# KSZ_Switch_Control.net
KiCad netlist of a schematic drawn in Altium Designer
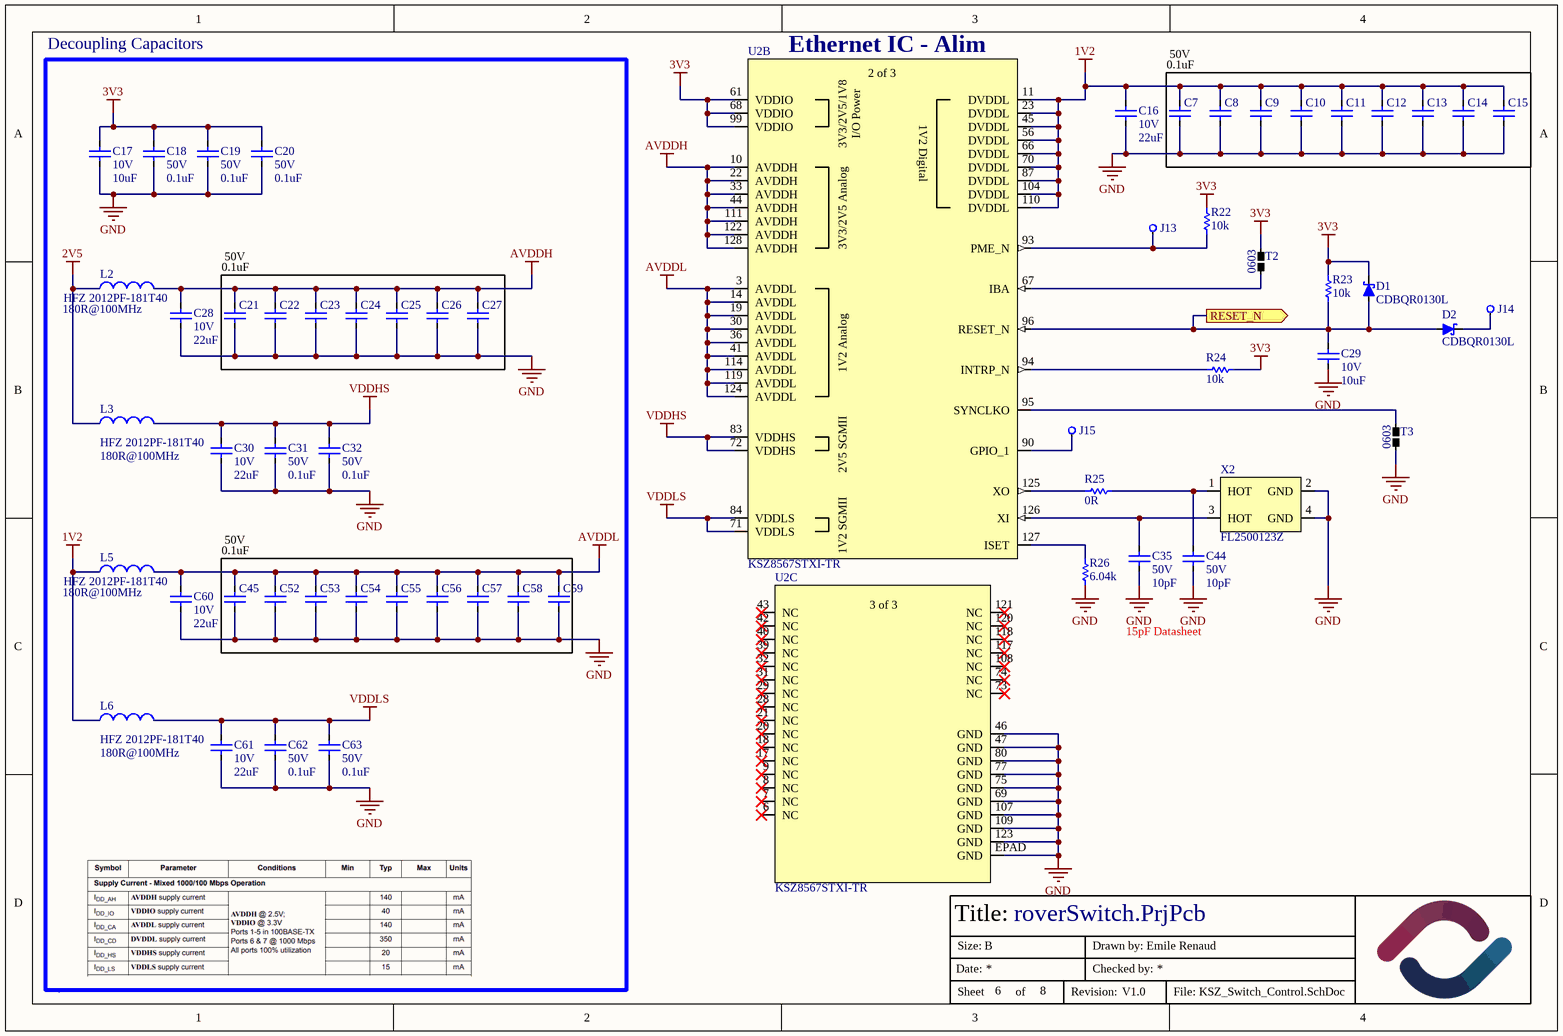
[diagram p0: KSZ_Switch_Control.SchDoc]

(export (version "E")
  (design (tool "Eeschema 10.0.6"))
  (components
    (comp (ref "C7")
      (value "Capacitor-0603-0.1uF-50V-X7R")
      (footprint "CAPACITOR-0603")
      (libsource (lib "Capacitors") (part "Capacitor-0603-0.1uF-50V-X7R"))
    )
    (comp (ref "C8")
      (value "Capacitor-0603-0.1uF-50V-X7R")
      (footprint "CAPACITOR-0603")
      (libsource (lib "Capacitors") (part "Capacitor-0603-0.1uF-50V-X7R"))
    )
    (comp (ref "C9")
      (value "Capacitor-0603-0.1uF-50V-X7R")
      (footprint "CAPACITOR-0603")
      (libsource (lib "Capacitors") (part "Capacitor-0603-0.1uF-50V-X7R"))
    )
    (comp (ref "C10")
      (value "Capacitor-0603-0.1uF-50V-X7R")
      (footprint "CAPACITOR-0603")
      (libsource (lib "Capacitors") (part "Capacitor-0603-0.1uF-50V-X7R"))
    )
    (comp (ref "C11")
      (value "Capacitor-0603-0.1uF-50V-X7R")
      (footprint "CAPACITOR-0603")
      (libsource (lib "Capacitors") (part "Capacitor-0603-0.1uF-50V-X7R"))
    )
    (comp (ref "C12")
      (value "Capacitor-0603-0.1uF-50V-X7R")
      (footprint "CAPACITOR-0603")
      (libsource (lib "Capacitors") (part "Capacitor-0603-0.1uF-50V-X7R"))
    )
    (comp (ref "C13")
      (value "Capacitor-0603-0.1uF-50V-X7R")
      (footprint "CAPACITOR-0603")
      (libsource (lib "Capacitors") (part "Capacitor-0603-0.1uF-50V-X7R"))
    )
    (comp (ref "C14")
      (value "Capacitor-0603-0.1uF-50V-X7R")
      (footprint "CAPACITOR-0603")
      (libsource (lib "Capacitors") (part "Capacitor-0603-0.1uF-50V-X7R"))
    )
    (comp (ref "C15")
      (value "Capacitor-0603-0.1uF-50V-X7R")
      (footprint "CAPACITOR-0603")
      (libsource (lib "Capacitors") (part "Capacitor-0603-0.1uF-50V-X7R"))
    )
    (comp (ref "C16")
      (value "22uF")
      (footprint "CAPACITOR-0603")
      (description "Capacitor-0603-22uF-10V-X5R")
      (fields (field (name "VOLT") "10V"))
      (libsource (lib "Capacitors") (part "Capacitor-0603-22uF-10V-X5R"))
    )
    (comp (ref "C17")
      (value "10uF")
      (footprint "CAPACITOR-0603")
      (description "10 µF ±20% 10V Ceramic Capacitor X5R 0603 (1608 Metric)")
      (fields (field (name "VOLT") "10V") (field (name "Comment") "Capacitor-0603-10uF-10V-X5R"))
      (libsource (lib "Capacitors") (part "Capacitor-0603-10uF-10V-X5R"))
    )
    (comp (ref "C18")
      (value "0.1uF")
      (footprint "CAPACITOR-0603")
      (description "Capacitor-0603-0.1uF-50V-X7R")
      (fields (field (name "VOLT") "50V"))
      (libsource (lib "Capacitors") (part "Capacitor-0603-0.1uF-50V-X7R"))
    )
    (comp (ref "C19")
      (value "0.1uF")
      (footprint "CAPACITOR-0603")
      (description "Capacitor-0603-0.1uF-50V-X7R")
      (fields (field (name "VOLT") "50V"))
      (libsource (lib "Capacitors") (part "Capacitor-0603-0.1uF-50V-X7R"))
    )
    (comp (ref "C20")
      (value "0.1uF")
      (footprint "CAPACITOR-0603")
      (description "Capacitor-0603-0.1uF-50V-X7R")
      (fields (field (name "VOLT") "50V"))
      (libsource (lib "Capacitors") (part "Capacitor-0603-0.1uF-50V-X7R"))
    )
    (comp (ref "C21")
      (value "Capacitor-0603-0.1uF-50V-X7R")
      (footprint "CAPACITOR-0603")
      (libsource (lib "Capacitors") (part "Capacitor-0603-0.1uF-50V-X7R"))
    )
    (comp (ref "C22")
      (value "Capacitor-0603-0.1uF-50V-X7R")
      (footprint "CAPACITOR-0603")
      (libsource (lib "Capacitors") (part "Capacitor-0603-0.1uF-50V-X7R"))
    )
    (comp (ref "C23")
      (value "Capacitor-0603-0.1uF-50V-X7R")
      (footprint "CAPACITOR-0603")
      (libsource (lib "Capacitors") (part "Capacitor-0603-0.1uF-50V-X7R"))
    )
    (comp (ref "C24")
      (value "Capacitor-0603-0.1uF-50V-X7R")
      (footprint "CAPACITOR-0603")
      (libsource (lib "Capacitors") (part "Capacitor-0603-0.1uF-50V-X7R"))
    )
    (comp (ref "C25")
      (value "Capacitor-0603-0.1uF-50V-X7R")
      (footprint "CAPACITOR-0603")
      (libsource (lib "Capacitors") (part "Capacitor-0603-0.1uF-50V-X7R"))
    )
    (comp (ref "C26")
      (value "Capacitor-0603-0.1uF-50V-X7R")
      (footprint "CAPACITOR-0603")
      (libsource (lib "Capacitors") (part "Capacitor-0603-0.1uF-50V-X7R"))
    )
    (comp (ref "C27")
      (value "Capacitor-0603-0.1uF-50V-X7R")
      (footprint "CAPACITOR-0603")
      (libsource (lib "Capacitors") (part "Capacitor-0603-0.1uF-50V-X7R"))
    )
    (comp (ref "C28")
      (value "22uF")
      (footprint "CAPACITOR-0603")
      (description "Capacitor-0603-22uF-10V-X5R")
      (fields (field (name "VOLT") "10V"))
      (libsource (lib "Capacitors") (part "Capacitor-0603-22uF-10V-X5R"))
    )
    (comp (ref "C29")
      (value "10uF")
      (footprint "CAPACITOR-0603")
      (description "10 µF ±20% 10V Ceramic Capacitor X5R 0603 (1608 Metric)")
      (fields (field (name "VOLT") "10V") (field (name "Comment") "Capacitor-0603-10uF-10V-X5R"))
      (libsource (lib "Capacitors") (part "Capacitor-0603-10uF-10V-X5R"))
    )
    (comp (ref "C30")
      (value "22uF")
      (footprint "CAPACITOR-0603")
      (description "Capacitor-0603-22uF-10V-X5R")
      (fields (field (name "VOLT") "10V"))
      (libsource (lib "Capacitors") (part "Capacitor-0603-22uF-10V-X5R"))
    )
    (comp (ref "C31")
      (value "0.1uF")
      (footprint "CAPACITOR-0603")
      (description "Capacitor-0603-0.1uF-50V-X7R")
      (fields (field (name "VOLT") "50V"))
      (libsource (lib "Capacitors") (part "Capacitor-0603-0.1uF-50V-X7R"))
    )
    (comp (ref "C32")
      (value "0.1uF")
      (footprint "CAPACITOR-0603")
      (description "Capacitor-0603-0.1uF-50V-X7R")
      (fields (field (name "VOLT") "50V"))
      (libsource (lib "Capacitors") (part "Capacitor-0603-0.1uF-50V-X7R"))
    )
    (comp (ref "C35")
      (value "10pF")
      (footprint "CAPACITOR-0402")
      (description "Capacitor-0402-10pF-50V-C0G")
      (fields (field (name "VOLT") "50V"))
      (libsource (lib "Capacitors") (part "Capacitor-0402-10pF-50V-C0G"))
    )
    (comp (ref "C44")
      (value "10pF")
      (footprint "CAPACITOR-0402")
      (description "Capacitor-0402-10pF-50V-C0G")
      (fields (field (name "VOLT") "50V"))
      (libsource (lib "Capacitors") (part "Capacitor-0402-10pF-50V-C0G"))
    )
    (comp (ref "C45")
      (value "Capacitor-0603-0.1uF-50V-X7R")
      (footprint "CAPACITOR-0603")
      (libsource (lib "Capacitors") (part "Capacitor-0603-0.1uF-50V-X7R"))
    )
    (comp (ref "C52")
      (value "Capacitor-0603-0.1uF-50V-X7R")
      (footprint "CAPACITOR-0603")
      (libsource (lib "Capacitors") (part "Capacitor-0603-0.1uF-50V-X7R"))
    )
    (comp (ref "C53")
      (value "Capacitor-0603-0.1uF-50V-X7R")
      (footprint "CAPACITOR-0603")
      (libsource (lib "Capacitors") (part "Capacitor-0603-0.1uF-50V-X7R"))
    )
    (comp (ref "C54")
      (value "Capacitor-0603-0.1uF-50V-X7R")
      (footprint "CAPACITOR-0603")
      (libsource (lib "Capacitors") (part "Capacitor-0603-0.1uF-50V-X7R"))
    )
    (comp (ref "C55")
      (value "Capacitor-0603-0.1uF-50V-X7R")
      (footprint "CAPACITOR-0603")
      (libsource (lib "Capacitors") (part "Capacitor-0603-0.1uF-50V-X7R"))
    )
    (comp (ref "C56")
      (value "Capacitor-0603-0.1uF-50V-X7R")
      (footprint "CAPACITOR-0603")
      (libsource (lib "Capacitors") (part "Capacitor-0603-0.1uF-50V-X7R"))
    )
    (comp (ref "C57")
      (value "Capacitor-0603-0.1uF-50V-X7R")
      (footprint "CAPACITOR-0603")
      (libsource (lib "Capacitors") (part "Capacitor-0603-0.1uF-50V-X7R"))
    )
    (comp (ref "C58")
      (value "Capacitor-0603-0.1uF-50V-X7R")
      (footprint "CAPACITOR-0603")
      (libsource (lib "Capacitors") (part "Capacitor-0603-0.1uF-50V-X7R"))
    )
    (comp (ref "C59")
      (value "Capacitor-0603-0.1uF-50V-X7R")
      (footprint "CAPACITOR-0603")
      (libsource (lib "Capacitors") (part "Capacitor-0603-0.1uF-50V-X7R"))
    )
    (comp (ref "C60")
      (value "22uF")
      (footprint "CAPACITOR-0603")
      (description "Capacitor-0603-22uF-10V-X5R")
      (fields (field (name "VOLT") "10V"))
      (libsource (lib "Capacitors") (part "Capacitor-0603-22uF-10V-X5R"))
    )
    (comp (ref "C61")
      (value "22uF")
      (footprint "CAPACITOR-0603")
      (description "Capacitor-0603-22uF-10V-X5R")
      (fields (field (name "VOLT") "10V"))
      (libsource (lib "Capacitors") (part "Capacitor-0603-22uF-10V-X5R"))
    )
    (comp (ref "C62")
      (value "0.1uF")
      (footprint "CAPACITOR-0603")
      (description "Capacitor-0603-0.1uF-50V-X7R")
      (fields (field (name "VOLT") "50V"))
      (libsource (lib "Capacitors") (part "Capacitor-0603-0.1uF-50V-X7R"))
    )
    (comp (ref "C63")
      (value "0.1uF")
      (footprint "CAPACITOR-0603")
      (description "Capacitor-0603-0.1uF-50V-X7R")
      (fields (field (name "VOLT") "50V"))
      (libsource (lib "Capacitors") (part "Capacitor-0603-0.1uF-50V-X7R"))
    )
    (comp (ref "D1")
      (value "CDBQR0130L")
      (footprint "Diode-0402")
      (description "Diode SCHOTTKY  30 V 100mA Surface Mount 0402/SOD-923F")
      (libsource (lib "diodes") (part "CDBQR0130L"))
    )
    (comp (ref "D2")
      (value "CDBQR0130L")
      (footprint "Diode-0402")
      (description "Diode SCHOTTKY  30 V 100mA Surface Mount 0402/SOD-923F")
      (libsource (lib "diodes") (part "CDBQR0130L"))
    )
    (comp (ref "J13")
      (value "hole")
      (footprint "PCB_Footprints:PAD-0.53MM")
      (description "PAD for 28 AWG Solid Wire")
      (libsource (lib "JumpersAndHoles") (part "PAD 0.53mm AWG28-Solid"))
    )
    (comp (ref "J14")
      (value "hole")
      (footprint "PCB_Footprints:PAD-0.53MM")
      (description "PAD for 28 AWG Solid Wire")
      (libsource (lib "JumpersAndHoles") (part "PAD 0.53mm AWG28-Solid"))
    )
    (comp (ref "J15")
      (value "hole")
      (footprint "PCB_Footprints:PAD-0.53MM")
      (description "PAD for 28 AWG Solid Wire")
      (libsource (lib "JumpersAndHoles") (part "PAD 0.53mm AWG28-Solid"))
    )
    (comp (ref "L2")
      (value "HFZ 2012PF-181T40")
      (footprint "CAPACITOR-0805")
      (description "180 Ohms @ 100 MHz 1 Power Line Ferrite Bead 0805 (2012 Metric) 4A 20mOhm")
      (fields (field (name "ALTIUM_VALUE") "180R@100MHz"))
      (libsource (lib "Inductors") (part "HFZ 2012PF-181T40"))
    )
    (comp (ref "L3")
      (value "HFZ 2012PF-181T40")
      (footprint "CAPACITOR-0805")
      (description "180 Ohms @ 100 MHz 1 Power Line Ferrite Bead 0805 (2012 Metric) 4A 20mOhm")
      (fields (field (name "ALTIUM_VALUE") "180R@100MHz"))
      (libsource (lib "Inductors") (part "HFZ 2012PF-181T40"))
    )
    (comp (ref "L5")
      (value "HFZ 2012PF-181T40")
      (footprint "CAPACITOR-0805")
      (description "180 Ohms @ 100 MHz 1 Power Line Ferrite Bead 0805 (2012 Metric) 4A 20mOhm")
      (fields (field (name "ALTIUM_VALUE") "180R@100MHz"))
      (libsource (lib "Inductors") (part "HFZ 2012PF-181T40"))
    )
    (comp (ref "L6")
      (value "HFZ 2012PF-181T40")
      (footprint "CAPACITOR-0805")
      (description "180 Ohms @ 100 MHz 1 Power Line Ferrite Bead 0805 (2012 Metric) 4A 20mOhm")
      (fields (field (name "ALTIUM_VALUE") "180R@100MHz"))
      (libsource (lib "Inductors") (part "HFZ 2012PF-181T40"))
    )
    (comp (ref "R22")
      (value "10k")
      (footprint "Resistor-0603")
      (description "Resistor0603-10k")
      (fields (field (name "Comment") "SMT resistor"))
      (libsource (lib "Resistors") (part "Resistor-0603-10k"))
    )
    (comp (ref "R23")
      (value "10k")
      (footprint "Resistor-0603")
      (description "Resistor0603-10k")
      (fields (field (name "Comment") "SMT resistor"))
      (libsource (lib "Resistors") (part "Resistor-0603-10k"))
    )
    (comp (ref "R24")
      (value "10k")
      (footprint "Resistor-0603")
      (description "Resistor0603-10k")
      (fields (field (name "Comment") "SMT resistor"))
      (libsource (lib "Resistors") (part "Resistor-0603-10k"))
    )
    (comp (ref "R25")
      (value "0R")
      (footprint "Resistor-0402")
      (description "Resistor-0402-0R")
      (fields (field (name "Comment") "SMT resistor"))
      (libsource (lib "Resistors") (part "Resistor-0402-0R"))
    )
    (comp (ref "R26")
      (value "6.04k")
      (footprint "Resistor-0603")
      (description "Resistor-0603-6.04k")
      (fields (field (name "Comment") "SMT resistor"))
      (libsource (lib "Resistors") (part "Resistor-0603-6.04k"))
    )
    (comp (ref "T2")
      (value "NetTie_0603")
      (footprint "NetTie-0603-short")
      (libsource (lib "JumpersAndHoles") (part "NetTie_0603_Short"))
    )
    (comp (ref "T3")
      (value "NetTie_0603_Short")
      (footprint "NetTie-0603-short")
      (libsource (lib "JumpersAndHoles") (part "NetTie_0603_Short"))
    )
    (comp (ref "U2")
      (value "KSZ8567STXI-TR")
      (footprint "TQFP128_EP_6XX_MCH-M")
      (description "IC ETHERNET SWITCH 7PORT 128TQFP")
      (libsource (lib "Ethernet") (part "KSZ8567STXI-TR"))
    )
    (comp (ref "X2")
      (value "FL2500123Z")
      (footprint "4-SMD")
      (description "25 MHz ±30ppm Crystal 20pF 50 Ohms 4-SMD, No Lead")
      (libsource (lib "Crystals") (part "FL2500123Z"))
    )
  )
  (nets
    (net (code "1") (name "/RESET_N") (class "Default")
      (node (ref "C29") (pin "2") (pinfunction "2_2") (pintype "passive"))
      (node (ref "D1") (pin "1") (pinfunction "A_1") (pintype "passive"))
      (node (ref "D2") (pin "1") (pinfunction "A_1") (pintype "passive"))
      (node (ref "R23") (pin "1") (pinfunction "1_1") (pintype "passive"))
      (node (ref "U2") (pin "96") (pinfunction "RESET_N_96") (pintype "input"))
    )
    (net (code "2") (name "1V2") (class "Default")
      (node (ref "C10") (pin "2") (pinfunction "2_2") (pintype "passive"))
      (node (ref "C11") (pin "2") (pinfunction "2_2") (pintype "passive"))
      (node (ref "C12") (pin "2") (pinfunction "2_2") (pintype "passive"))
      (node (ref "C13") (pin "2") (pinfunction "2_2") (pintype "passive"))
      (node (ref "C14") (pin "2") (pinfunction "2_2") (pintype "passive"))
      (node (ref "C15") (pin "2") (pinfunction "2_2") (pintype "passive"))
      (node (ref "C16") (pin "2") (pinfunction "2_2") (pintype "passive"))
      (node (ref "C7") (pin "2") (pinfunction "2_2") (pintype "passive"))
      (node (ref "C8") (pin "2") (pinfunction "2_2") (pintype "passive"))
      (node (ref "C9") (pin "2") (pinfunction "2_2") (pintype "passive"))
      (node (ref "L5") (pin "1") (pinfunction "1_1") (pintype "passive"))
      (node (ref "L6") (pin "1") (pinfunction "1_1") (pintype "passive"))
      (node (ref "U2") (pin "104") (pinfunction "DVDDL_104") (pintype "power_in"))
      (node (ref "U2") (pin "11") (pinfunction "DVDDL_11") (pintype "power_in"))
      (node (ref "U2") (pin "110") (pinfunction "DVDDL_110") (pintype "power_in"))
      (node (ref "U2") (pin "23") (pinfunction "DVDDL_23") (pintype "power_in"))
      (node (ref "U2") (pin "45") (pinfunction "DVDDL_45") (pintype "power_in"))
      (node (ref "U2") (pin "56") (pinfunction "DVDDL_56") (pintype "power_in"))
      (node (ref "U2") (pin "66") (pinfunction "DVDDL_66") (pintype "power_in"))
      (node (ref "U2") (pin "70") (pinfunction "DVDDL_70") (pintype "power_in"))
      (node (ref "U2") (pin "87") (pinfunction "DVDDL_87") (pintype "power_in"))
    )
    (net (code "3") (name "2V5") (class "Default")
      (node (ref "L2") (pin "1") (pinfunction "1_1") (pintype "passive"))
      (node (ref "L3") (pin "1") (pinfunction "1_1") (pintype "passive"))
    )
    (net (code "4") (name "3V3") (class "Default")
      (node (ref "C17") (pin "2") (pinfunction "2_2") (pintype "passive"))
      (node (ref "C18") (pin "2") (pinfunction "2_2") (pintype "passive"))
      (node (ref "C19") (pin "2") (pinfunction "2_2") (pintype "passive"))
      (node (ref "C20") (pin "2") (pinfunction "2_2") (pintype "passive"))
      (node (ref "D1") (pin "2") (pinfunction "K_2") (pintype "passive"))
      (node (ref "R22") (pin "2") (pinfunction "2_2") (pintype "passive"))
      (node (ref "R23") (pin "2") (pinfunction "2_2") (pintype "passive"))
      (node (ref "R24") (pin "2") (pinfunction "2_2") (pintype "passive"))
      (node (ref "T2") (pin "1") (pinfunction "1_1") (pintype "passive"))
      (node (ref "U2") (pin "61") (pinfunction "VDDIO_61") (pintype "power_in"))
      (node (ref "U2") (pin "68") (pinfunction "VDDIO_68") (pintype "power_in"))
      (node (ref "U2") (pin "99") (pinfunction "VDDIO_99") (pintype "power_in"))
    )
    (net (code "5") (name "AVDDH") (class "Default")
      (node (ref "C21") (pin "2") (pinfunction "2_2") (pintype "passive"))
      (node (ref "C22") (pin "2") (pinfunction "2_2") (pintype "passive"))
      (node (ref "C23") (pin "2") (pinfunction "2_2") (pintype "passive"))
      (node (ref "C24") (pin "2") (pinfunction "2_2") (pintype "passive"))
      (node (ref "C25") (pin "2") (pinfunction "2_2") (pintype "passive"))
      (node (ref "C26") (pin "2") (pinfunction "2_2") (pintype "passive"))
      (node (ref "C27") (pin "2") (pinfunction "2_2") (pintype "passive"))
      (node (ref "C28") (pin "2") (pinfunction "2_2") (pintype "passive"))
      (node (ref "L2") (pin "2") (pinfunction "2_2") (pintype "passive"))
      (node (ref "U2") (pin "10") (pinfunction "AVDDH_10") (pintype "power_in"))
      (node (ref "U2") (pin "111") (pinfunction "AVDDH_111") (pintype "power_in"))
      (node (ref "U2") (pin "122") (pinfunction "AVDDH_122") (pintype "power_in"))
      (node (ref "U2") (pin "128") (pinfunction "AVDDH_128") (pintype "power_in"))
      (node (ref "U2") (pin "22") (pinfunction "AVDDH_22") (pintype "power_in"))
      (node (ref "U2") (pin "33") (pinfunction "AVDDH_33") (pintype "power_in"))
      (node (ref "U2") (pin "44") (pinfunction "AVDDH_44") (pintype "power_in"))
    )
    (net (code "6") (name "AVDDL") (class "Default")
      (node (ref "C45") (pin "2") (pinfunction "2_2") (pintype "passive"))
      (node (ref "C52") (pin "2") (pinfunction "2_2") (pintype "passive"))
      (node (ref "C53") (pin "2") (pinfunction "2_2") (pintype "passive"))
      (node (ref "C54") (pin "2") (pinfunction "2_2") (pintype "passive"))
      (node (ref "C55") (pin "2") (pinfunction "2_2") (pintype "passive"))
      (node (ref "C56") (pin "2") (pinfunction "2_2") (pintype "passive"))
      (node (ref "C57") (pin "2") (pinfunction "2_2") (pintype "passive"))
      (node (ref "C58") (pin "2") (pinfunction "2_2") (pintype "passive"))
      (node (ref "C59") (pin "2") (pinfunction "2_2") (pintype "passive"))
      (node (ref "C60") (pin "2") (pinfunction "2_2") (pintype "passive"))
      (node (ref "L5") (pin "2") (pinfunction "2_2") (pintype "passive"))
      (node (ref "U2") (pin "114") (pinfunction "AVDDL_114") (pintype "power_in"))
      (node (ref "U2") (pin "119") (pinfunction "AVDDL_119") (pintype "power_in"))
      (node (ref "U2") (pin "124") (pinfunction "AVDDL_124") (pintype "power_in"))
      (node (ref "U2") (pin "14") (pinfunction "AVDDL_14") (pintype "power_in"))
      (node (ref "U2") (pin "19") (pinfunction "AVDDL_19") (pintype "power_in"))
      (node (ref "U2") (pin "3") (pinfunction "AVDDL_3") (pintype "power_in"))
      (node (ref "U2") (pin "30") (pinfunction "AVDDL_30") (pintype "power_in"))
      (node (ref "U2") (pin "36") (pinfunction "AVDDL_36") (pintype "power_in"))
      (node (ref "U2") (pin "41") (pinfunction "AVDDL_41") (pintype "power_in"))
    )
    (net (code "7") (name "GND") (class "Default")
      (node (ref "C10") (pin "1") (pinfunction "1_1") (pintype "passive"))
      (node (ref "C11") (pin "1") (pinfunction "1_1") (pintype "passive"))
      (node (ref "C12") (pin "1") (pinfunction "1_1") (pintype "passive"))
      (node (ref "C13") (pin "1") (pinfunction "1_1") (pintype "passive"))
      (node (ref "C14") (pin "1") (pinfunction "1_1") (pintype "passive"))
      (node (ref "C15") (pin "1") (pinfunction "1_1") (pintype "passive"))
      (node (ref "C16") (pin "1") (pinfunction "1_1") (pintype "passive"))
      (node (ref "C17") (pin "1") (pinfunction "1_1") (pintype "passive"))
      (node (ref "C18") (pin "1") (pinfunction "1_1") (pintype "passive"))
      (node (ref "C19") (pin "1") (pinfunction "1_1") (pintype "passive"))
      (node (ref "C20") (pin "1") (pinfunction "1_1") (pintype "passive"))
      (node (ref "C21") (pin "1") (pinfunction "1_1") (pintype "passive"))
      (node (ref "C22") (pin "1") (pinfunction "1_1") (pintype "passive"))
      (node (ref "C23") (pin "1") (pinfunction "1_1") (pintype "passive"))
      (node (ref "C24") (pin "1") (pinfunction "1_1") (pintype "passive"))
      (node (ref "C25") (pin "1") (pinfunction "1_1") (pintype "passive"))
      (node (ref "C26") (pin "1") (pinfunction "1_1") (pintype "passive"))
      (node (ref "C27") (pin "1") (pinfunction "1_1") (pintype "passive"))
      (node (ref "C28") (pin "1") (pinfunction "1_1") (pintype "passive"))
      (node (ref "C29") (pin "1") (pinfunction "1_1") (pintype "passive"))
      (node (ref "C30") (pin "1") (pinfunction "1_1") (pintype "passive"))
      (node (ref "C31") (pin "1") (pinfunction "1_1") (pintype "passive"))
      (node (ref "C32") (pin "1") (pinfunction "1_1") (pintype "passive"))
      (node (ref "C35") (pin "1") (pinfunction "1_1") (pintype "passive"))
      (node (ref "C44") (pin "1") (pinfunction "1_1") (pintype "passive"))
      (node (ref "C45") (pin "1") (pinfunction "1_1") (pintype "passive"))
      (node (ref "C52") (pin "1") (pinfunction "1_1") (pintype "passive"))
      (node (ref "C53") (pin "1") (pinfunction "1_1") (pintype "passive"))
      (node (ref "C54") (pin "1") (pinfunction "1_1") (pintype "passive"))
      (node (ref "C55") (pin "1") (pinfunction "1_1") (pintype "passive"))
      (node (ref "C56") (pin "1") (pinfunction "1_1") (pintype "passive"))
      (node (ref "C57") (pin "1") (pinfunction "1_1") (pintype "passive"))
      (node (ref "C58") (pin "1") (pinfunction "1_1") (pintype "passive"))
      (node (ref "C59") (pin "1") (pinfunction "1_1") (pintype "passive"))
      (node (ref "C60") (pin "1") (pinfunction "1_1") (pintype "passive"))
      (node (ref "C61") (pin "1") (pinfunction "1_1") (pintype "passive"))
      (node (ref "C62") (pin "1") (pinfunction "1_1") (pintype "passive"))
      (node (ref "C63") (pin "1") (pinfunction "1_1") (pintype "passive"))
      (node (ref "C7") (pin "1") (pinfunction "1_1") (pintype "passive"))
      (node (ref "C8") (pin "1") (pinfunction "1_1") (pintype "passive"))
      (node (ref "C9") (pin "1") (pinfunction "1_1") (pintype "passive"))
      (node (ref "R26") (pin "1") (pinfunction "1_1") (pintype "passive"))
      (node (ref "T3") (pin "2") (pinfunction "2_2") (pintype "passive"))
      (node (ref "U2") (pin "107") (pinfunction "GND_107") (pintype "power_in"))
      (node (ref "U2") (pin "109") (pinfunction "GND_109") (pintype "power_in"))
      (node (ref "U2") (pin "123") (pinfunction "GND_123") (pintype "power_in"))
      (node (ref "U2") (pin "46") (pinfunction "GND_46") (pintype "power_in"))
      (node (ref "U2") (pin "47") (pinfunction "GND_47") (pintype "power_in"))
      (node (ref "U2") (pin "69") (pinfunction "GND_69") (pintype "power_in"))
      (node (ref "U2") (pin "75") (pinfunction "GND_75") (pintype "power_in"))
      (node (ref "U2") (pin "77") (pinfunction "GND_77") (pintype "power_in"))
      (node (ref "U2") (pin "80") (pinfunction "GND_80") (pintype "power_in"))
      (node (ref "U2") (pin "EPAD") (pinfunction "GND_EPAD") (pintype "power_in"))
      (node (ref "X2") (pin "2") (pinfunction "GND_2") (pintype "passive"))
      (node (ref "X2") (pin "4") (pinfunction "GND_4") (pintype "passive"))
    )
    (net (code "8") (name "Net-(C44-Pad2)") (class "Default")
      (node (ref "C44") (pin "2") (pinfunction "2_2") (pintype "passive"))
      (node (ref "R25") (pin "2") (pinfunction "2_2") (pintype "passive"))
      (node (ref "X2") (pin "1") (pinfunction "HOT_1") (pintype "passive"))
    )
    (net (code "9") (name "Net-(D2-K)") (class "Default")
      (node (ref "D2") (pin "2") (pinfunction "K_2") (pintype "passive"))
      (node (ref "J14") (pin "1") (pinfunction "1_1") (pintype "passive"))
    )
    (net (code "10") (name "Net-(U2B-GPIO_1)") (class "Default")
      (node (ref "J15") (pin "1") (pinfunction "1_1") (pintype "passive"))
      (node (ref "U2") (pin "90") (pinfunction "GPIO_1_90") (pintype "bidirectional"))
    )
    (net (code "11") (name "Net-(U2B-IBA)") (class "Default")
      (node (ref "T2") (pin "2") (pinfunction "2_2") (pintype "passive"))
      (node (ref "U2") (pin "67") (pinfunction "IBA_67") (pintype "input"))
    )
    (net (code "12") (name "Net-(U2B-INTRP_N)") (class "Default")
      (node (ref "R24") (pin "1") (pinfunction "1_1") (pintype "passive"))
      (node (ref "U2") (pin "94") (pinfunction "INTRP_N_94") (pintype "output"))
    )
    (net (code "13") (name "Net-(U2B-ISET)") (class "Default")
      (node (ref "R26") (pin "2") (pinfunction "2_2") (pintype "passive"))
      (node (ref "U2") (pin "127") (pinfunction "ISET_127") (pintype "passive"))
    )
    (net (code "14") (name "Net-(U2B-PME_N)") (class "Default")
      (node (ref "J13") (pin "1") (pinfunction "1_1") (pintype "passive"))
      (node (ref "R22") (pin "1") (pinfunction "1_1") (pintype "passive"))
      (node (ref "U2") (pin "93") (pinfunction "PME_N_93") (pintype "output"))
    )
    (net (code "15") (name "Net-(U2B-SYNCLKO)") (class "Default")
      (node (ref "T3") (pin "1") (pinfunction "1_1") (pintype "passive"))
      (node (ref "U2") (pin "95") (pinfunction "SYNCLKO_95") (pintype "bidirectional"))
    )
    (net (code "16") (name "Net-(U2B-XI)") (class "Default")
      (node (ref "C35") (pin "2") (pinfunction "2_2") (pintype "passive"))
      (node (ref "U2") (pin "126") (pinfunction "XI_126") (pintype "input"))
      (node (ref "X2") (pin "3") (pinfunction "HOT_3") (pintype "passive"))
    )
    (net (code "17") (name "Net-(U2B-XO)") (class "Default")
      (node (ref "R25") (pin "1") (pinfunction "1_1") (pintype "passive"))
      (node (ref "U2") (pin "125") (pinfunction "XO_125") (pintype "output"))
    )
    (net (code "18") (name "VDDHS") (class "Default")
      (node (ref "C30") (pin "2") (pinfunction "2_2") (pintype "passive"))
      (node (ref "C31") (pin "2") (pinfunction "2_2") (pintype "passive"))
      (node (ref "C32") (pin "2") (pinfunction "2_2") (pintype "passive"))
      (node (ref "L3") (pin "2") (pinfunction "2_2") (pintype "passive"))
      (node (ref "U2") (pin "72") (pinfunction "VDDHS_72") (pintype "power_in"))
      (node (ref "U2") (pin "83") (pinfunction "VDDHS_83") (pintype "power_in"))
    )
    (net (code "19") (name "VDDLS") (class "Default")
      (node (ref "C61") (pin "2") (pinfunction "2_2") (pintype "passive"))
      (node (ref "C62") (pin "2") (pinfunction "2_2") (pintype "passive"))
      (node (ref "C63") (pin "2") (pinfunction "2_2") (pintype "passive"))
      (node (ref "L6") (pin "2") (pinfunction "2_2") (pintype "passive"))
      (node (ref "U2") (pin "71") (pinfunction "VDDLS_71") (pintype "power_in"))
      (node (ref "U2") (pin "84") (pinfunction "VDDLS_84") (pintype "power_in"))
    )
    (net (code "20") (name "unconnected-(U2C-NC-Pad6)") (class "Default")
      (node (ref "U2") (pin "6") (pinfunction "NC_6") (pintype "passive+no_connect"))
    )
    (net (code "21") (name "unconnected-(U2C-NC-Pad7)") (class "Default")
      (node (ref "U2") (pin "7") (pinfunction "NC_7") (pintype "passive+no_connect"))
    )
    (net (code "22") (name "unconnected-(U2C-NC-Pad8)") (class "Default")
      (node (ref "U2") (pin "8") (pinfunction "NC_8") (pintype "passive+no_connect"))
    )
    (net (code "23") (name "unconnected-(U2C-NC-Pad9)") (class "Default")
      (node (ref "U2") (pin "9") (pinfunction "NC_9") (pintype "passive+no_connect"))
    )
    (net (code "24") (name "unconnected-(U2C-NC-Pad17)") (class "Default")
      (node (ref "U2") (pin "17") (pinfunction "NC_17") (pintype "passive+no_connect"))
    )
    (net (code "25") (name "unconnected-(U2C-NC-Pad18)") (class "Default")
      (node (ref "U2") (pin "18") (pinfunction "NC_18") (pintype "passive+no_connect"))
    )
    (net (code "26") (name "unconnected-(U2C-NC-Pad20)") (class "Default")
      (node (ref "U2") (pin "20") (pinfunction "NC_20") (pintype "passive+no_connect"))
    )
    (net (code "27") (name "unconnected-(U2C-NC-Pad21)") (class "Default")
      (node (ref "U2") (pin "21") (pinfunction "NC_21") (pintype "passive+no_connect"))
    )
    (net (code "28") (name "unconnected-(U2C-NC-Pad28)") (class "Default")
      (node (ref "U2") (pin "28") (pinfunction "NC_28") (pintype "passive+no_connect"))
    )
    (net (code "29") (name "unconnected-(U2C-NC-Pad29)") (class "Default")
      (node (ref "U2") (pin "29") (pinfunction "NC_29") (pintype "passive+no_connect"))
    )
    (net (code "30") (name "unconnected-(U2C-NC-Pad31)") (class "Default")
      (node (ref "U2") (pin "31") (pinfunction "NC_31") (pintype "passive+no_connect"))
    )
    (net (code "31") (name "unconnected-(U2C-NC-Pad32)") (class "Default")
      (node (ref "U2") (pin "32") (pinfunction "NC_32") (pintype "passive+no_connect"))
    )
    (net (code "32") (name "unconnected-(U2C-NC-Pad39)") (class "Default")
      (node (ref "U2") (pin "39") (pinfunction "NC_39") (pintype "passive+no_connect"))
    )
    (net (code "33") (name "unconnected-(U2C-NC-Pad40)") (class "Default")
      (node (ref "U2") (pin "40") (pinfunction "NC_40") (pintype "passive+no_connect"))
    )
    (net (code "34") (name "unconnected-(U2C-NC-Pad42)") (class "Default")
      (node (ref "U2") (pin "42") (pinfunction "NC_42") (pintype "passive+no_connect"))
    )
    (net (code "35") (name "unconnected-(U2C-NC-Pad43)") (class "Default")
      (node (ref "U2") (pin "43") (pinfunction "NC_43") (pintype "passive+no_connect"))
    )
    (net (code "36") (name "unconnected-(U2C-NC-Pad73)") (class "Default")
      (node (ref "U2") (pin "73") (pinfunction "NC_73") (pintype "passive+no_connect"))
    )
    (net (code "37") (name "unconnected-(U2C-NC-Pad74)") (class "Default")
      (node (ref "U2") (pin "74") (pinfunction "NC_74") (pintype "passive+no_connect"))
    )
    (net (code "38") (name "unconnected-(U2C-NC-Pad108)") (class "Default")
      (node (ref "U2") (pin "108") (pinfunction "NC_108") (pintype "passive+no_connect"))
    )
    (net (code "39") (name "unconnected-(U2C-NC-Pad117)") (class "Default")
      (node (ref "U2") (pin "117") (pinfunction "NC_117") (pintype "passive+no_connect"))
    )
    (net (code "40") (name "unconnected-(U2C-NC-Pad118)") (class "Default")
      (node (ref "U2") (pin "118") (pinfunction "NC_118") (pintype "passive+no_connect"))
    )
    (net (code "41") (name "unconnected-(U2C-NC-Pad120)") (class "Default")
      (node (ref "U2") (pin "120") (pinfunction "NC_120") (pintype "passive+no_connect"))
    )
    (net (code "42") (name "unconnected-(U2C-NC-Pad121)") (class "Default")
      (node (ref "U2") (pin "121") (pinfunction "NC_121") (pintype "passive+no_connect"))
    )
  )
)
